# communicator_v2p1.net
KiCad netlist of a schematic drawn in EAGLE
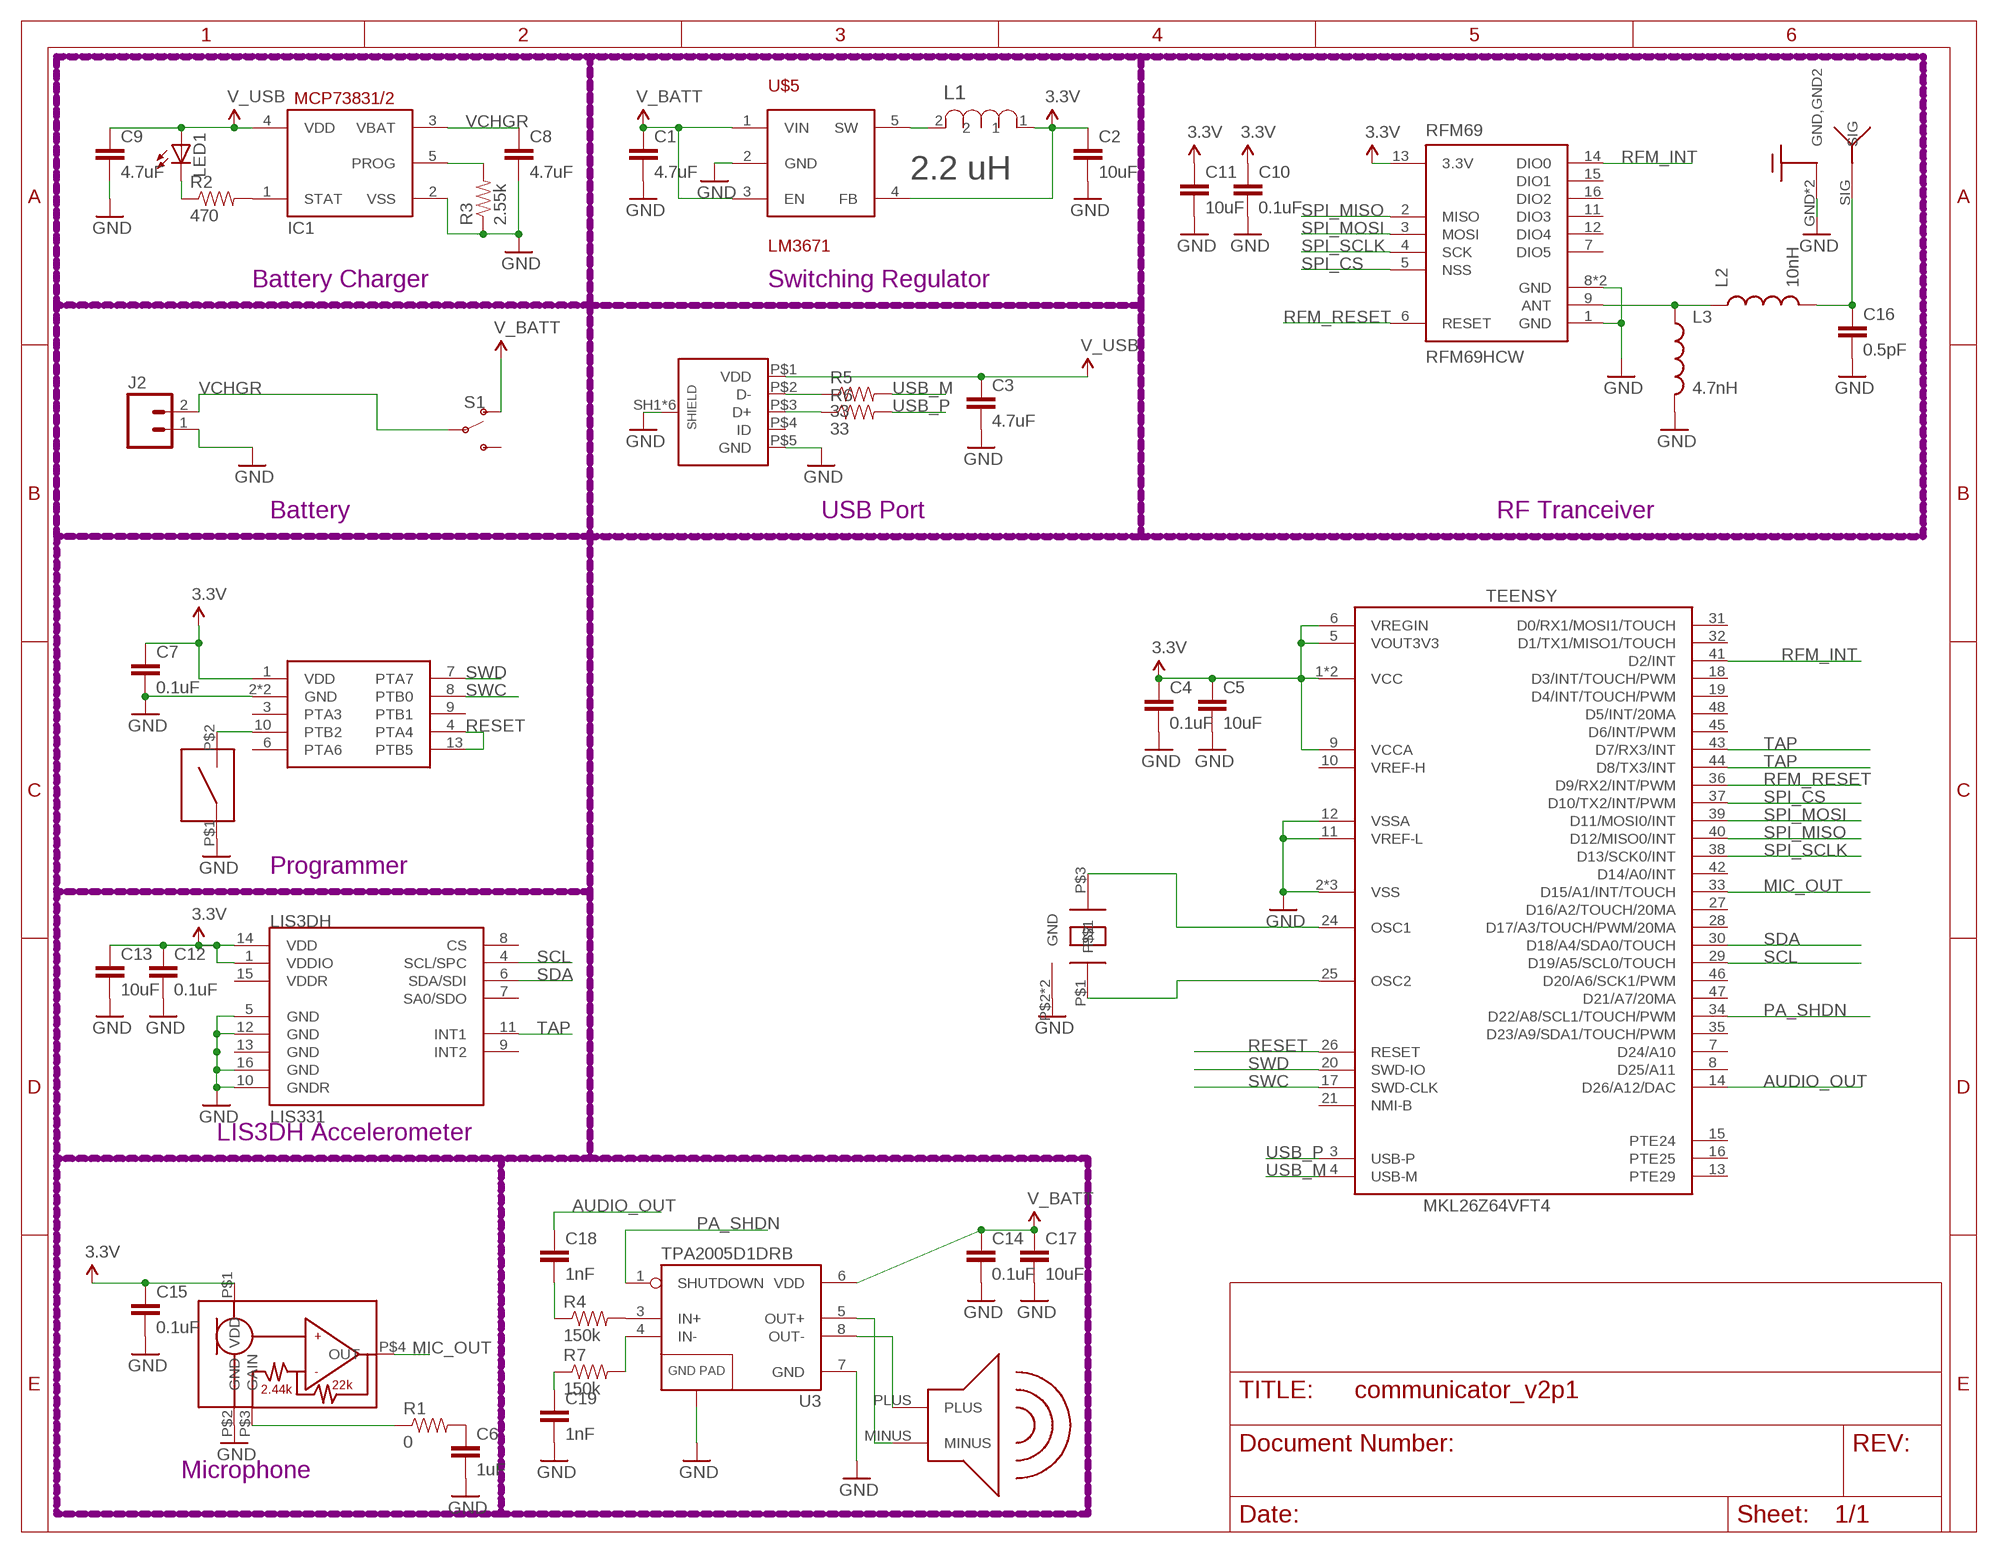
[diagram p0: schematic, sheet 1]

(export (version "E")
  (design (tool "Eeschema 10.0.6"))
  (components
    (comp (ref "3X3MM1")
      (value "CURRENT_BOOTLOADER3X3MM")
      (footprint "eagle-import:QFN50P300X300X100-17N")
      (libsource (lib "eagle-import") (part "CURRENT_BOOTLOADER3X3MM"))
    )
    (comp (ref "C1")
      (value "4.7uF")
      (footprint "eagle-import:0603-CAP")
      (libsource (lib "eagle-import") (part "0.1UF-25V(+80/-20%)(0603)"))
    )
    (comp (ref "C2")
      (value "10uF")
      (footprint "eagle-import:0603-CAP")
      (libsource (lib "eagle-import") (part "2.2UF-10V-20%(0603)"))
    )
    (comp (ref "C3")
      (value "4.7uF")
      (footprint "eagle-import:0603-CAP")
      (libsource (lib "eagle-import") (part "2.2UF-10V-20%(0603)"))
    )
    (comp (ref "C4")
      (value "0.1uF")
      (footprint "eagle-import:0603-CAP")
      (libsource (lib "eagle-import") (part "0.1UF-25V(+80/-20%)(0603)"))
    )
    (comp (ref "C5")
      (value "10uF")
      (footprint "eagle-import:0603-CAP")
      (libsource (lib "eagle-import") (part "10UF-6.3V-20%(0603)"))
    )
    (comp (ref "C6")
      (value "1uF")
      (footprint "eagle-import:0603-CAP")
      (libsource (lib "eagle-import") (part "0.1UF-25V(+80/-20%)(0603)"))
    )
    (comp (ref "C7")
      (value "0.1uF")
      (footprint "eagle-import:0603-CAP")
      (libsource (lib "eagle-import") (part "0.1UF-25V(+80/-20%)(0603)"))
    )
    (comp (ref "C8")
      (value "4.7uF")
      (footprint "eagle-import:0603-CAP")
      (libsource (lib "eagle-import") (part "4.7UF-6.3V-10%(0603)0603"))
    )
    (comp (ref "C9")
      (value "4.7uF")
      (footprint "eagle-import:0603-CAP")
      (libsource (lib "eagle-import") (part "4.7UF-6.3V-10%(0603)0603"))
    )
    (comp (ref "C10")
      (value "0.1uF")
      (footprint "eagle-import:0603-CAP")
      (libsource (lib "eagle-import") (part "0.1UF-25V(+80/-20%)(0603)"))
    )
    (comp (ref "C11")
      (value "10uF")
      (footprint "eagle-import:0603-CAP")
      (libsource (lib "eagle-import") (part "10UF-6.3V-20%(0603)"))
    )
    (comp (ref "C12")
      (value "0.1uF")
      (footprint "eagle-import:0603-CAP")
      (libsource (lib "eagle-import") (part "0.1UF-25V(+80/-20%)(0603)"))
    )
    (comp (ref "C13")
      (value "10uF")
      (footprint "eagle-import:0603-CAP")
      (libsource (lib "eagle-import") (part "10UF-6.3V-20%(0603)"))
    )
    (comp (ref "C14")
      (value "0.1uF")
      (footprint "eagle-import:0603-CAP")
      (libsource (lib "eagle-import") (part "0.1UF-25V(+80/-20%)(0603)"))
    )
    (comp (ref "C15")
      (value "0.1uF")
      (footprint "eagle-import:0603-CAP")
      (libsource (lib "eagle-import") (part "0.1UF-25V(+80/-20%)(0603)"))
    )
    (comp (ref "C16")
      (value "0.5pF")
      (footprint "eagle-import:0603-CAP")
      (libsource (lib "eagle-import") (part "0.75PF-50V(-/+.25PF)(0603)"))
    )
    (comp (ref "C17")
      (value "10uF")
      (footprint "eagle-import:0603-CAP")
      (libsource (lib "eagle-import") (part "10UF-6.3V-20%(0603)"))
    )
    (comp (ref "C18")
      (value "1nF")
      (footprint "eagle-import:0603-CAP")
      (libsource (lib "eagle-import") (part "0.1UF-25V(+80/-20%)(0603)"))
    )
    (comp (ref "C19")
      (value "1nF")
      (footprint "eagle-import:0603-CAP")
      (libsource (lib "eagle-import") (part "0.1UF-25V(+80/-20%)(0603)"))
    )
    (comp (ref "IC1")
      (value "MCP73831/OT")
      (footprint "eagle-import:SOT23-5L")
      (libsource (lib "eagle-import") (part "MCP73831/OT"))
    )
    (comp (ref "J2")
      (value "M02PTH")
      (footprint "eagle-import:1X02")
      (libsource (lib "eagle-import") (part "M02PTH"))
    )
    (comp (ref "L1")
      (value "2.2 uH")
      (footprint "eagle-import:INDC3225X22N")
      (fields (field (name "MPN") "PM1210-2R2J-RC") (field (name "TOLERANCE") "±5 %"))
      (libsource (lib "eagle-import") (part "PM1210-2R2J-RC"))
    )
    (comp (ref "L2")
      (value "10nH")
      (footprint "eagle-import:0603")
      (libsource (lib "eagle-import") (part "INDUCTOR0603"))
    )
    (comp (ref "L3")
      (value "4.7nH")
      (footprint "eagle-import:0603")
      (libsource (lib "eagle-import") (part "INDUCTOR0603"))
    )
    (comp (ref "LED1")
      (value "LEDCHIPLED_0805")
      (footprint "eagle-import:CHIPLED_0805")
      (libsource (lib "eagle-import") (part "LEDCHIPLED_0805"))
    )
    (comp (ref "LIS3DH")
      (value "LIS331")
      (footprint "eagle-import:LGA16-3MM")
      (libsource (lib "eagle-import") (part "LIS331"))
    )
    (comp (ref "R1")
      (value "0")
      (footprint "eagle-import:0603-RES")
      (libsource (lib "eagle-import") (part "33OHM1/10W1%(0603)"))
    )
    (comp (ref "R2")
      (value "470")
      (footprint "eagle-import:0603-RES")
      (libsource (lib "eagle-import") (part "470OHM1/10W1%(0603)"))
    )
    (comp (ref "R3")
      (value "2.55k")
      (footprint "eagle-import:0603-RES")
      (libsource (lib "eagle-import") (part "2.55KOHM-1/10W-1%(0603)"))
    )
    (comp (ref "R4")
      (value "150k")
      (footprint "eagle-import:0603-RES")
      (libsource (lib "eagle-import") (part "33OHM1/10W1%(0603)"))
    )
    (comp (ref "R5")
      (value "33")
      (footprint "eagle-import:0603-RES")
      (libsource (lib "eagle-import") (part "33OHM1/10W1%(0603)"))
    )
    (comp (ref "R6")
      (value "33")
      (footprint "eagle-import:0603-RES")
      (libsource (lib "eagle-import") (part "33OHM1/10W1%(0603)"))
    )
    (comp (ref "R7")
      (value "150k")
      (footprint "eagle-import:0603-RES")
      (libsource (lib "eagle-import") (part "33OHM1/10W1%(0603)"))
    )
    (comp (ref "RFM69")
      (value "RFM69HCW")
      (footprint "eagle-import:RFM69HCW-XXXS2")
      (libsource (lib "eagle-import") (part "RFM69HCW"))
    )
    (comp (ref "S1")
      (value "SWITCH-SPDT-SMD-RIGHT-ANGLE")
      (footprint "eagle-import:SWITCH_SPST_SMD_A")
      (libsource (lib "eagle-import") (part "SWITCH-SPDT-SMD-RIGHT-ANGLE"))
    )
    (comp (ref "TEENSY")
      (value "MKL26Z64VFT4")
      (footprint "eagle-import:QFN50P700X700X100-49N")
      (libsource (lib "eagle-import") (part "MKL26Z64VFT4"))
    )
    (comp (ref "U$1")
      (value "ANTENNA_915MHZ")
      (footprint "eagle-import:ANTENNA_915MHZ")
      (libsource (lib "eagle-import") (part "ANTENNA_915MHZ"))
    )
    (comp (ref "U$2")
      (value "MICROPHONE")
      (footprint "eagle-import:SPU0414HR5H-SB")
      (libsource (lib "eagle-import") (part "MICROPHONE"))
    )
    (comp (ref "U$3")
      (value "SPEAKER")
      (footprint "eagle-import:PSR1511N08S3K")
      (libsource (lib "eagle-import") (part "SPEAKER"))
    )
    (comp (ref "U$4")
      (value "KXT131LHS")
      (footprint "eagle-import:KXT131LHS")
      (libsource (lib "eagle-import") (part "KXT131LHS"))
    )
    (comp (ref "U$5")
      (value "LM3671")
      (footprint "eagle-import:SOT23-5")
      (libsource (lib "eagle-import") (part "LM3671"))
    )
    (comp (ref "U$8")
      (value "MICRO_USB_B")
      (footprint "eagle-import:MICRO_USB_B")
      (libsource (lib "eagle-import") (part "MICRO_USB_B"))
    )
    (comp (ref "U$9")
      (value "TSX-3225")
      (footprint "eagle-import:TSX-3225")
      (libsource (lib "eagle-import") (part "TSX-3225"))
    )
    (comp (ref "U3")
      (value "TPA2005D1DRB")
      (footprint "eagle-import:QFN-8_PAD")
      (libsource (lib "eagle-import") (part "TPA2005D1DRB"))
    )
  )
  (nets
    (net (code "1") (name "/AUDIO_OUT") (class "Default")
      (node (ref "C18") (pin "1") (pinfunction "1_1") (pintype "passive"))
      (node (ref "TEENSY") (pin "14") (pinfunction "D26/A12/DAC_14") (pintype "bidirectional"))
    )
    (net (code "2") (name "/MIC_OUT") (class "Default")
      (node (ref "TEENSY") (pin "33") (pinfunction "D15/A1/INT/TOUCH_33") (pintype "bidirectional"))
      (node (ref "U$2") (pin "P$4") (pinfunction "OUT_P$4") (pintype "bidirectional"))
    )
    (net (code "3") (name "/PA_SHDN") (class "Default")
      (node (ref "TEENSY") (pin "34") (pinfunction "D22/A8/SCL1/TOUCH/PWM_34") (pintype "bidirectional"))
      (node (ref "U3") (pin "1") (pinfunction "SHUTDOWN_1") (pintype "input"))
    )
    (net (code "4") (name "/RESET") (class "Default")
      (node (ref "3X3MM1") (pin "13") (pinfunction "PTB5_13") (pintype "bidirectional"))
      (node (ref "3X3MM1") (pin "4") (pinfunction "PTA4_4") (pintype "bidirectional"))
      (node (ref "TEENSY") (pin "26") (pinfunction "RESET_26") (pintype "bidirectional"))
    )
    (net (code "5") (name "/RFM_INT") (class "Default")
      (node (ref "RFM69") (pin "14") (pinfunction "DIO0_14") (pintype "bidirectional"))
      (node (ref "TEENSY") (pin "41") (pinfunction "D2/INT_41") (pintype "bidirectional"))
    )
    (net (code "6") (name "/RFM_RESET") (class "Default")
      (node (ref "RFM69") (pin "6") (pinfunction "RESET_6") (pintype "input"))
      (node (ref "TEENSY") (pin "36") (pinfunction "D9/RX2/INT/PWM_36") (pintype "bidirectional"))
    )
    (net (code "7") (name "/SCL") (class "Default")
      (node (ref "LIS3DH") (pin "4") (pinfunction "SCL/SPC_4") (pintype "bidirectional"))
      (node (ref "TEENSY") (pin "29") (pinfunction "D19/A5/SCL0/TOUCH_29") (pintype "bidirectional"))
    )
    (net (code "8") (name "/SDA") (class "Default")
      (node (ref "LIS3DH") (pin "6") (pinfunction "SDA/SDI_6") (pintype "bidirectional"))
      (node (ref "TEENSY") (pin "30") (pinfunction "D18/A4/SDA0/TOUCH_30") (pintype "bidirectional"))
    )
    (net (code "9") (name "/SPI_CS") (class "Default")
      (node (ref "RFM69") (pin "5") (pinfunction "NSS_5") (pintype "input"))
      (node (ref "TEENSY") (pin "37") (pinfunction "D10/TX2/INT/PWM_37") (pintype "bidirectional"))
    )
    (net (code "10") (name "/SPI_MISO") (class "Default")
      (node (ref "RFM69") (pin "2") (pinfunction "MISO_2") (pintype "bidirectional"))
      (node (ref "TEENSY") (pin "40") (pinfunction "D12/MISO0/INT_40") (pintype "bidirectional"))
    )
    (net (code "11") (name "/SPI_MOSI") (class "Default")
      (node (ref "RFM69") (pin "3") (pinfunction "MOSI_3") (pintype "input"))
      (node (ref "TEENSY") (pin "39") (pinfunction "D11/MOSI0/INT_39") (pintype "bidirectional"))
    )
    (net (code "12") (name "/SPI_SCLK") (class "Default")
      (node (ref "RFM69") (pin "4") (pinfunction "SCK_4") (pintype "input"))
      (node (ref "TEENSY") (pin "38") (pinfunction "D13/SCK0/INT_38") (pintype "bidirectional"))
    )
    (net (code "13") (name "/SWC") (class "Default")
      (node (ref "3X3MM1") (pin "8") (pinfunction "PTB0_8") (pintype "bidirectional"))
      (node (ref "TEENSY") (pin "17") (pinfunction "SWD-CLK_17") (pintype "bidirectional"))
    )
    (net (code "14") (name "/SWD") (class "Default")
      (node (ref "3X3MM1") (pin "7") (pinfunction "PTA7_7") (pintype "bidirectional"))
      (node (ref "TEENSY") (pin "20") (pinfunction "SWD-IO_20") (pintype "bidirectional"))
    )
    (net (code "15") (name "/TAP") (class "Default")
      (node (ref "LIS3DH") (pin "11") (pinfunction "INT1_11") (pintype "bidirectional"))
      (node (ref "TEENSY") (pin "43") (pinfunction "D7/RX3/INT_43") (pintype "bidirectional"))
      (node (ref "TEENSY") (pin "44") (pinfunction "D8/TX3/INT_44") (pintype "bidirectional"))
    )
    (net (code "16") (name "/USB_M") (class "Default")
      (node (ref "R5") (pin "2") (pinfunction "2_2") (pintype "passive"))
      (node (ref "TEENSY") (pin "4") (pinfunction "USB-M_4") (pintype "bidirectional"))
    )
    (net (code "17") (name "/USB_P") (class "Default")
      (node (ref "R6") (pin "2") (pinfunction "2_2") (pintype "passive"))
      (node (ref "TEENSY") (pin "3") (pinfunction "USB-P_3") (pintype "bidirectional"))
    )
    (net (code "18") (name "/VCHGR") (class "Default")
      (node (ref "C8") (pin "1") (pinfunction "1_1") (pintype "passive"))
      (node (ref "IC1") (pin "3") (pinfunction "VBAT_3") (pintype "bidirectional"))
      (node (ref "J2") (pin "2") (pinfunction "2_2") (pintype "passive"))
      (node (ref "S1") (pin "2") (pinfunction "P_2") (pintype "passive"))
    )
    (net (code "19") (name "3.3V") (class "Default")
      (node (ref "3X3MM1") (pin "1") (pinfunction "VDD_1") (pintype "bidirectional"))
      (node (ref "C10") (pin "1") (pinfunction "1_1") (pintype "passive"))
      (node (ref "C11") (pin "1") (pinfunction "1_1") (pintype "passive"))
      (node (ref "C12") (pin "1") (pinfunction "1_1") (pintype "passive"))
      (node (ref "C13") (pin "1") (pinfunction "1_1") (pintype "passive"))
      (node (ref "C15") (pin "1") (pinfunction "1_1") (pintype "passive"))
      (node (ref "C2") (pin "1") (pinfunction "1_1") (pintype "passive"))
      (node (ref "C4") (pin "1") (pinfunction "1_1") (pintype "passive"))
      (node (ref "C5") (pin "1") (pinfunction "1_1") (pintype "passive"))
      (node (ref "C7") (pin "1") (pinfunction "1_1") (pintype "passive"))
      (node (ref "L1") (pin "1") (pinfunction "1_1") (pintype "passive"))
      (node (ref "LIS3DH") (pin "1") (pinfunction "VDDIO_1") (pintype "bidirectional"))
      (node (ref "LIS3DH") (pin "14") (pinfunction "VDD_14") (pintype "bidirectional"))
      (node (ref "RFM69") (pin "13") (pinfunction "3.3V_13") (pintype "power_in"))
      (node (ref "TEENSY") (pin "1") (pinfunction "VCC_1") (pintype "bidirectional"))
      (node (ref "TEENSY") (pin "22") (pinfunction "VCC_22") (pintype "bidirectional"))
      (node (ref "TEENSY") (pin "5") (pinfunction "VOUT3V3_5") (pintype "bidirectional"))
      (node (ref "TEENSY") (pin "6") (pinfunction "VREGIN_6") (pintype "bidirectional"))
      (node (ref "TEENSY") (pin "9") (pinfunction "VCCA_9") (pintype "bidirectional"))
      (node (ref "U$2") (pin "P$1") (pinfunction "VDD_P$1") (pintype "bidirectional"))
      (node (ref "U$5") (pin "4") (pinfunction "FB_4") (pintype "bidirectional"))
    )
    (net (code "20") (name "GND") (class "Default")
      (node (ref "3X3MM1") (pin "17") (pinfunction "GND_17") (pintype "bidirectional"))
      (node (ref "3X3MM1") (pin "2") (pinfunction "GND_2") (pintype "bidirectional"))
      (node (ref "C1") (pin "2") (pinfunction "2_2") (pintype "passive"))
      (node (ref "C10") (pin "2") (pinfunction "2_2") (pintype "passive"))
      (node (ref "C11") (pin "2") (pinfunction "2_2") (pintype "passive"))
      (node (ref "C12") (pin "2") (pinfunction "2_2") (pintype "passive"))
      (node (ref "C13") (pin "2") (pinfunction "2_2") (pintype "passive"))
      (node (ref "C14") (pin "2") (pinfunction "2_2") (pintype "passive"))
      (node (ref "C15") (pin "2") (pinfunction "2_2") (pintype "passive"))
      (node (ref "C16") (pin "2") (pinfunction "2_2") (pintype "passive"))
      (node (ref "C17") (pin "2") (pinfunction "2_2") (pintype "passive"))
      (node (ref "C19") (pin "2") (pinfunction "2_2") (pintype "passive"))
      (node (ref "C2") (pin "2") (pinfunction "2_2") (pintype "passive"))
      (node (ref "C3") (pin "2") (pinfunction "2_2") (pintype "passive"))
      (node (ref "C4") (pin "2") (pinfunction "2_2") (pintype "passive"))
      (node (ref "C5") (pin "2") (pinfunction "2_2") (pintype "passive"))
      (node (ref "C6") (pin "2") (pinfunction "2_2") (pintype "passive"))
      (node (ref "C7") (pin "2") (pinfunction "2_2") (pintype "passive"))
      (node (ref "C8") (pin "2") (pinfunction "2_2") (pintype "passive"))
      (node (ref "C9") (pin "2") (pinfunction "2_2") (pintype "passive"))
      (node (ref "IC1") (pin "2") (pinfunction "VSS_2") (pintype "power_in"))
      (node (ref "J2") (pin "1") (pinfunction "1_1") (pintype "passive"))
      (node (ref "L3") (pin "2") (pinfunction "2_2") (pintype "passive"))
      (node (ref "LIS3DH") (pin "10") (pinfunction "GNDR_10") (pintype "bidirectional"))
      (node (ref "LIS3DH") (pin "12") (pinfunction "GND_12") (pintype "bidirectional"))
      (node (ref "LIS3DH") (pin "16") (pinfunction "GND_16") (pintype "bidirectional"))
      (node (ref "LIS3DH") (pin "5") (pinfunction "GND_5") (pintype "bidirectional"))
      (node (ref "R3") (pin "1") (pinfunction "1_1") (pintype "passive"))
      (node (ref "RFM69") (pin "1") (pinfunction "GND_1") (pintype "power_in"))
      (node (ref "RFM69") (pin "10") (pinfunction "GND_10") (pintype "power_in"))
      (node (ref "RFM69") (pin "8") (pinfunction "GND_8") (pintype "power_in"))
      (node (ref "TEENSY") (pin "11") (pinfunction "VREF-L_11") (pintype "bidirectional"))
      (node (ref "TEENSY") (pin "12") (pinfunction "VSSA_12") (pintype "bidirectional"))
      (node (ref "TEENSY") (pin "2") (pinfunction "VSS_2") (pintype "bidirectional"))
      (node (ref "TEENSY") (pin "23") (pinfunction "VSS_23") (pintype "bidirectional"))
      (node (ref "TEENSY") (pin "49") (pinfunction "VSS_49") (pintype "bidirectional"))
      (node (ref "U$1") (pin "GND") (pinfunction "GND,GND2_GND") (pintype "bidirectional"))
      (node (ref "U$1") (pin "GND2") (pinfunction "GND,GND2_GND2") (pintype "bidirectional"))
      (node (ref "U$2") (pin "P$2") (pinfunction "GND_P$2") (pintype "bidirectional"))
      (node (ref "U$4") (pin "P$1") (pinfunction "P$1_P$1") (pintype "bidirectional"))
      (node (ref "U$5") (pin "2") (pinfunction "GND_2") (pintype "bidirectional"))
      (node (ref "U$8") (pin "P$5") (pinfunction "GND_P$5") (pintype "bidirectional"))
      (node (ref "U$8") (pin "SH1") (pinfunction "SHIELD_SH1") (pintype "bidirectional"))
      (node (ref "U$8") (pin "SH2") (pinfunction "SHIELD_SH2") (pintype "bidirectional"))
      (node (ref "U$8") (pin "SH3") (pinfunction "SHIELD_SH3") (pintype "bidirectional"))
      (node (ref "U$8") (pin "SH4") (pinfunction "SHIELD_SH4") (pintype "bidirectional"))
      (node (ref "U$8") (pin "SH5") (pinfunction "SHIELD_SH5") (pintype "bidirectional"))
      (node (ref "U$8") (pin "SH6") (pinfunction "SHIELD_SH6") (pintype "bidirectional"))
      (node (ref "U$9") (pin "P$2") (pinfunction "GND_P$2") (pintype "bidirectional"))
      (node (ref "U$9") (pin "P$4") (pinfunction "GND_P$4") (pintype "bidirectional"))
      (node (ref "U3") (pin "10") (pinfunction "GND_10") (pintype "power_in"))
      (node (ref "U3") (pin "11") (pinfunction "GND_11") (pintype "power_in"))
      (node (ref "U3") (pin "12") (pinfunction "GND_12") (pintype "power_in"))
      (node (ref "U3") (pin "13") (pinfunction "GND_13") (pintype "power_in"))
      (node (ref "U3") (pin "7") (pinfunction "GND_7") (pintype "power_in"))
      (node (ref "U3") (pin "9") (pinfunction "GND_9") (pintype "power_in"))
    )
    (net (code "21") (name "Net-(3X3MM1-PTB2)") (class "Default")
      (node (ref "3X3MM1") (pin "10") (pinfunction "PTB2_10") (pintype "bidirectional"))
      (node (ref "U$4") (pin "P$2") (pinfunction "P$2_P$2") (pintype "bidirectional"))
    )
    (net (code "22") (name "Net-(C6-Pad1)") (class "Default")
      (node (ref "C6") (pin "1") (pinfunction "1_1") (pintype "passive"))
      (node (ref "R1") (pin "2") (pinfunction "2_2") (pintype "passive"))
    )
    (net (code "23") (name "Net-(C16-Pad1)") (class "Default")
      (node (ref "C16") (pin "1") (pinfunction "1_1") (pintype "passive"))
      (node (ref "L2") (pin "2") (pinfunction "2_2") (pintype "passive"))
      (node (ref "U$1") (pin "SIG") (pinfunction "SIG_SIG") (pintype "bidirectional"))
    )
    (net (code "24") (name "Net-(C18-Pad2)") (class "Default")
      (node (ref "C18") (pin "2") (pinfunction "2_2") (pintype "passive"))
      (node (ref "R4") (pin "1") (pinfunction "1_1") (pintype "passive"))
    )
    (net (code "25") (name "Net-(C19-Pad1)") (class "Default")
      (node (ref "C19") (pin "1") (pinfunction "1_1") (pintype "passive"))
      (node (ref "R7") (pin "1") (pinfunction "1_1") (pintype "passive"))
    )
    (net (code "26") (name "Net-(IC1-PROG)") (class "Default")
      (node (ref "IC1") (pin "5") (pinfunction "PROG_5") (pintype "input"))
      (node (ref "R3") (pin "2") (pinfunction "2_2") (pintype "passive"))
    )
    (net (code "27") (name "Net-(IC1-STAT)") (class "Default")
      (node (ref "IC1") (pin "1") (pinfunction "STAT_1") (pintype "output"))
      (node (ref "R2") (pin "2") (pinfunction "2_2") (pintype "passive"))
    )
    (net (code "28") (name "Net-(LED1-PadC)") (class "Default")
      (node (ref "LED1") (pin "C") (pinfunction "C_C") (pintype "passive"))
      (node (ref "R2") (pin "1") (pinfunction "1_1") (pintype "passive"))
    )
    (net (code "29") (name "Net-(RFM69-ANT)") (class "Default")
      (node (ref "L2") (pin "1") (pinfunction "1_1") (pintype "passive"))
      (node (ref "L3") (pin "1") (pinfunction "1_1") (pintype "passive"))
      (node (ref "RFM69") (pin "9") (pinfunction "ANT_9") (pintype "passive"))
    )
    (net (code "30") (name "Net-(TEENSY-OSC1)") (class "Default")
      (node (ref "TEENSY") (pin "24") (pinfunction "OSC1_24") (pintype "bidirectional"))
      (node (ref "U$9") (pin "P$3") (pinfunction "P$2_P$3") (pintype "bidirectional"))
    )
    (net (code "31") (name "Net-(TEENSY-OSC2)") (class "Default")
      (node (ref "TEENSY") (pin "25") (pinfunction "OSC2_25") (pintype "bidirectional"))
      (node (ref "U$9") (pin "P$1") (pinfunction "P$1_P$1") (pintype "bidirectional"))
    )
    (net (code "32") (name "Net-(U$2-GAIN)") (class "Default")
      (node (ref "R1") (pin "1") (pinfunction "1_1") (pintype "passive"))
      (node (ref "U$2") (pin "P$3") (pinfunction "GAIN_P$3") (pintype "bidirectional"))
    )
    (net (code "33") (name "Net-(U$5-SW)") (class "Default")
      (node (ref "L1") (pin "2") (pinfunction "2_2") (pintype "passive"))
      (node (ref "U$5") (pin "5") (pinfunction "SW_5") (pintype "bidirectional"))
    )
    (net (code "34") (name "Net-(U$8-D+)") (class "Default")
      (node (ref "R6") (pin "1") (pinfunction "1_1") (pintype "passive"))
      (node (ref "U$8") (pin "P$3") (pinfunction "D+_P$3") (pintype "bidirectional"))
    )
    (net (code "35") (name "Net-(U$8-D-)") (class "Default")
      (node (ref "R5") (pin "1") (pinfunction "1_1") (pintype "passive"))
      (node (ref "U$8") (pin "P$2") (pinfunction "D-_P$2") (pintype "bidirectional"))
    )
    (net (code "36") (name "Net-(U3-IN+)") (class "Default")
      (node (ref "R4") (pin "2") (pinfunction "2_2") (pintype "passive"))
      (node (ref "U3") (pin "3") (pinfunction "IN+_3") (pintype "bidirectional"))
    )
    (net (code "37") (name "Net-(U3-IN-)") (class "Default")
      (node (ref "R7") (pin "2") (pinfunction "2_2") (pintype "passive"))
      (node (ref "U3") (pin "4") (pinfunction "IN-_4") (pintype "bidirectional"))
    )
    (net (code "38") (name "Net-(U3-OUT+)") (class "Default")
      (node (ref "U$3") (pin "MINUS") (pinfunction "MINUS_MINUS") (pintype "bidirectional"))
      (node (ref "U3") (pin "5") (pinfunction "OUT+_5") (pintype "bidirectional"))
    )
    (net (code "39") (name "Net-(U3-OUT-)") (class "Default")
      (node (ref "U$3") (pin "PLUS") (pinfunction "PLUS_PLUS") (pintype "bidirectional"))
      (node (ref "U3") (pin "8") (pinfunction "OUT-_8") (pintype "bidirectional"))
    )
    (net (code "40") (name "V_BATT") (class "Default")
      (node (ref "C1") (pin "1") (pinfunction "1_1") (pintype "passive"))
      (node (ref "C14") (pin "1") (pinfunction "1_1") (pintype "passive"))
      (node (ref "C17") (pin "1") (pinfunction "1_1") (pintype "passive"))
      (node (ref "S1") (pin "1") (pinfunction "O_1") (pintype "passive"))
      (node (ref "U$5") (pin "1") (pinfunction "VIN_1") (pintype "bidirectional"))
      (node (ref "U$5") (pin "3") (pinfunction "EN_3") (pintype "bidirectional"))
      (node (ref "U3") (pin "6") (pinfunction "VDD_6") (pintype "power_in"))
    )
    (net (code "41") (name "V_USB") (class "Default")
      (node (ref "C3") (pin "1") (pinfunction "1_1") (pintype "passive"))
      (node (ref "C9") (pin "1") (pinfunction "1_1") (pintype "passive"))
      (node (ref "IC1") (pin "4") (pinfunction "VDD_4") (pintype "power_in"))
      (node (ref "LED1") (pin "A") (pinfunction "A_A") (pintype "passive"))
      (node (ref "U$8") (pin "P$1") (pinfunction "VDD_P$1") (pintype "bidirectional"))
    )
    (net (code "42") (name "unconnected-(3X3MM1-PTA3-Pad3)") (class "Default")
      (node (ref "3X3MM1") (pin "3") (pinfunction "PTA3_3") (pintype "bidirectional"))
    )
    (net (code "43") (name "unconnected-(3X3MM1-PTA6-Pad6)") (class "Default")
      (node (ref "3X3MM1") (pin "6") (pinfunction "PTA6_6") (pintype "bidirectional"))
    )
    (net (code "44") (name "unconnected-(3X3MM1-PTB1-Pad9)") (class "Default")
      (node (ref "3X3MM1") (pin "9") (pinfunction "PTB1_9") (pintype "bidirectional"))
    )
    (net (code "45") (name "unconnected-(LIS3DH-CS-Pad8)") (class "Default")
      (node (ref "LIS3DH") (pin "8") (pinfunction "CS_8") (pintype "bidirectional"))
    )
    (net (code "46") (name "unconnected-(LIS3DH-GND-Pad13)") (class "Default")
      (node (ref "LIS3DH") (pin "13") (pinfunction "GND_13") (pintype "bidirectional"))
    )
    (net (code "47") (name "unconnected-(LIS3DH-INT2-Pad9)") (class "Default")
      (node (ref "LIS3DH") (pin "9") (pinfunction "INT2_9") (pintype "bidirectional"))
    )
    (net (code "48") (name "unconnected-(LIS3DH-SA0{slash}SDO-Pad7)") (class "Default")
      (node (ref "LIS3DH") (pin "7") (pinfunction "SA0/SDO_7") (pintype "bidirectional"))
    )
    (net (code "49") (name "unconnected-(LIS3DH-VDDR-Pad15)") (class "Default")
      (node (ref "LIS3DH") (pin "15") (pinfunction "VDDR_15") (pintype "bidirectional"))
    )
    (net (code "50") (name "unconnected-(RFM69-DIO1-Pad15)") (class "Default")
      (node (ref "RFM69") (pin "15") (pinfunction "DIO1_15") (pintype "bidirectional"))
    )
    (net (code "51") (name "unconnected-(RFM69-DIO2-Pad16)") (class "Default")
      (node (ref "RFM69") (pin "16") (pinfunction "DIO2_16") (pintype "bidirectional"))
    )
    (net (code "52") (name "unconnected-(RFM69-DIO3-Pad11)") (class "Default")
      (node (ref "RFM69") (pin "11") (pinfunction "DIO3_11") (pintype "bidirectional"))
    )
    (net (code "53") (name "unconnected-(RFM69-DIO4-Pad12)") (class "Default")
      (node (ref "RFM69") (pin "12") (pinfunction "DIO4_12") (pintype "bidirectional"))
    )
    (net (code "54") (name "unconnected-(RFM69-DIO5-Pad7)") (class "Default")
      (node (ref "RFM69") (pin "7") (pinfunction "DIO5_7") (pintype "bidirectional"))
    )
    (net (code "55") (name "unconnected-(S1-S-Pad3)") (class "Default")
      (node (ref "S1") (pin "3") (pinfunction "S_3") (pintype "passive"))
    )
    (net (code "56") (name "unconnected-(TEENSY-D0{slash}RX1{slash}MOSI1{slash}TOUCH-Pad31)") (class "Default")
      (node (ref "TEENSY") (pin "31") (pinfunction "D0/RX1/MOSI1/TOUCH_31") (pintype "bidirectional"))
    )
    (net (code "57") (name "unconnected-(TEENSY-D1{slash}TX1{slash}MISO1{slash}TOUCH-Pad32)") (class "Default")
      (node (ref "TEENSY") (pin "32") (pinfunction "D1/TX1/MISO1/TOUCH_32") (pintype "bidirectional"))
    )
    (net (code "58") (name "unconnected-(TEENSY-D3{slash}INT{slash}TOUCH{slash}PWM-Pad18)") (class "Default")
      (node (ref "TEENSY") (pin "18") (pinfunction "D3/INT/TOUCH/PWM_18") (pintype "bidirectional"))
    )
    (net (code "59") (name "unconnected-(TEENSY-D4{slash}INT{slash}TOUCH{slash}PWM-Pad19)") (class "Default")
      (node (ref "TEENSY") (pin "19") (pinfunction "D4/INT/TOUCH/PWM_19") (pintype "bidirectional"))
    )
    (net (code "60") (name "unconnected-(TEENSY-D5{slash}INT{slash}20MA-Pad48)") (class "Default")
      (node (ref "TEENSY") (pin "48") (pinfunction "D5/INT/20MA_48") (pintype "bidirectional"))
    )
    (net (code "61") (name "unconnected-(TEENSY-D6{slash}INT{slash}PWM-Pad45)") (class "Default")
      (node (ref "TEENSY") (pin "45") (pinfunction "D6/INT/PWM_45") (pintype "bidirectional"))
    )
    (net (code "62") (name "unconnected-(TEENSY-D14{slash}A0{slash}INT-Pad42)") (class "Default")
      (node (ref "TEENSY") (pin "42") (pinfunction "D14/A0/INT_42") (pintype "bidirectional"))
    )
    (net (code "63") (name "unconnected-(TEENSY-D16{slash}A2{slash}TOUCH{slash}20MA-Pad27)") (class "Default")
      (node (ref "TEENSY") (pin "27") (pinfunction "D16/A2/TOUCH/20MA_27") (pintype "bidirectional"))
    )
    (net (code "64") (name "unconnected-(TEENSY-D17{slash}A3{slash}TOUCH{slash}PWM{slash}20MA-Pad28)") (class "Default")
      (node (ref "TEENSY") (pin "28") (pinfunction "D17/A3/TOUCH/PWM/20MA_28") (pintype "bidirectional"))
    )
    (net (code "65") (name "unconnected-(TEENSY-D20{slash}A6{slash}SCK1{slash}PWM-Pad46)") (class "Default")
      (node (ref "TEENSY") (pin "46") (pinfunction "D20/A6/SCK1/PWM_46") (pintype "bidirectional"))
    )
    (net (code "66") (name "unconnected-(TEENSY-D21{slash}A7{slash}20MA-Pad47)") (class "Default")
      (node (ref "TEENSY") (pin "47") (pinfunction "D21/A7/20MA_47") (pintype "bidirectional"))
    )
    (net (code "67") (name "unconnected-(TEENSY-D23{slash}A9{slash}SDA1{slash}TOUCH{slash}PWM-Pad35)") (class "Default")
      (node (ref "TEENSY") (pin "35") (pinfunction "D23/A9/SDA1/TOUCH/PWM_35") (pintype "bidirectional"))
    )
    (net (code "68") (name "unconnected-(TEENSY-D24{slash}A10-Pad7)") (class "Default")
      (node (ref "TEENSY") (pin "7") (pinfunction "D24/A10_7") (pintype "bidirectional"))
    )
    (net (code "69") (name "unconnected-(TEENSY-D25{slash}A11-Pad8)") (class "Default")
      (node (ref "TEENSY") (pin "8") (pinfunction "D25/A11_8") (pintype "bidirectional"))
    )
    (net (code "70") (name "unconnected-(TEENSY-NMI-B-Pad21)") (class "Default")
      (node (ref "TEENSY") (pin "21") (pinfunction "NMI-B_21") (pintype "bidirectional"))
    )
    (net (code "71") (name "unconnected-(TEENSY-PTE24-Pad15)") (class "Default")
      (node (ref "TEENSY") (pin "15") (pinfunction "PTE24_15") (pintype "bidirectional"))
    )
    (net (code "72") (name "unconnected-(TEENSY-PTE25-Pad16)") (class "Default")
      (node (ref "TEENSY") (pin "16") (pinfunction "PTE25_16") (pintype "bidirectional"))
    )
    (net (code "73") (name "unconnected-(TEENSY-PTE29-Pad13)") (class "Default")
      (node (ref "TEENSY") (pin "13") (pinfunction "PTE29_13") (pintype "bidirectional"))
    )
    (net (code "74") (name "unconnected-(TEENSY-VREF-H-Pad10)") (class "Default")
      (node (ref "TEENSY") (pin "10") (pinfunction "VREF-H_10") (pintype "bidirectional"))
    )
    (net (code "75") (name "unconnected-(U$8-ID-PadP$4)") (class "Default")
      (node (ref "U$8") (pin "P$4") (pinfunction "ID_P$4") (pintype "bidirectional"))
    )
  )
)
